# TestBoard.net
KiCad netlist of a schematic drawn in Altium Designer
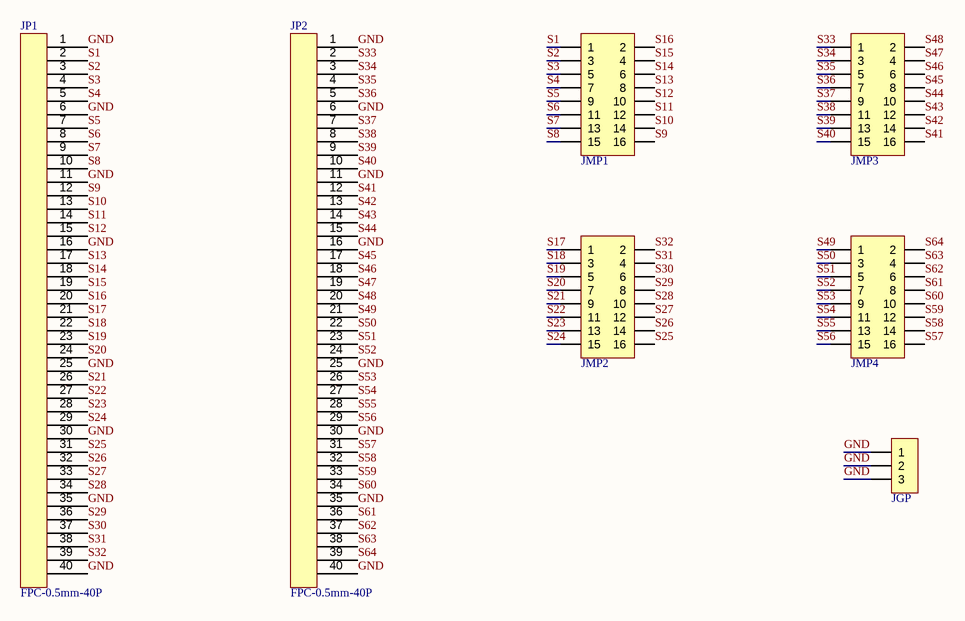
[diagram p0: TestBoard.SchDoc]

(export (version "E")
  (design (tool "Eeschema 10.0.6"))
  (components
    (comp (ref "JGP")
      (value "HDR-1X3")
      (footprint "XH2.54-LI-3P")
      (description "3P接插件")
      (fields (field (name "版权归属") "封装库来自淘宝 ID：黄晶宝石"))
      (libsource (lib "5.4 - 接插件-脚距2.54 (100mil) ") (part "Header 3"))
    )
    (comp (ref "JMP1")
      (value "Header 8X2")
      (footprint "IDC2.54-LI-2x8P")
      (description "8*2P接插件")
      (fields (field (name "版权归属") "封装库来自淘宝 ID：黄晶宝石"))
      (libsource (lib "5.4 - 接插件-脚距2.54 (100mil) ") (part "Header 8X2"))
    )
    (comp (ref "JMP2")
      (value "Header 8X2")
      (footprint "IDC2.54-LI-2x8P")
      (description "8*2P接插件")
      (fields (field (name "版权归属") "封装库来自淘宝 ID：黄晶宝石"))
      (libsource (lib "5.4 - 接插件-脚距2.54 (100mil) ") (part "Header 8X2"))
    )
    (comp (ref "JMP3")
      (value "Header 8X2")
      (footprint "IDC2.54-LI-2x8P")
      (description "8*2P接插件")
      (fields (field (name "版权归属") "封装库来自淘宝 ID：黄晶宝石"))
      (libsource (lib "5.4 - 接插件-脚距2.54 (100mil) ") (part "Header 8X2"))
    )
    (comp (ref "JMP4")
      (value "Header 8X2")
      (footprint "IDC2.54-LI-2x8P")
      (description "8*2P接插件")
      (fields (field (name "版权归属") "封装库来自淘宝 ID：黄晶宝石"))
      (libsource (lib "5.4 - 接插件-脚距2.54 (100mil) ") (part "Header 8X2"))
    )
    (comp (ref "JP1")
      (value "FPC-0.5mm-40P")
      (footprint "FPC0.5 2H-WS-40P")
      (description "FPC Connector 0.5mm 40PIN")
      (libsource (lib "CustomizedComponents") (part "FPC-0.5mm-40P"))
    )
    (comp (ref "JP2")
      (value "FPC-0.5mm-40P")
      (footprint "FPC0.5 2H-WS-40P")
      (description "FPC Connector 0.5mm 40PIN")
      (libsource (lib "CustomizedComponents") (part "FPC-0.5mm-40P"))
    )
  )
  (nets
    (net (code "1") (name "/GND") (class "Default")
      (node (ref "JGP") (pin "1") (pinfunction "1_1") (pintype "passive"))
      (node (ref "JGP") (pin "2") (pinfunction "2_2") (pintype "passive"))
      (node (ref "JGP") (pin "3") (pinfunction "3_3") (pintype "passive"))
      (node (ref "JP1") (pin "1") (pintype "passive"))
      (node (ref "JP1") (pin "11") (pintype "passive"))
      (node (ref "JP1") (pin "16") (pintype "passive"))
      (node (ref "JP1") (pin "25") (pintype "passive"))
      (node (ref "JP1") (pin "30") (pintype "passive"))
      (node (ref "JP1") (pin "35") (pintype "passive"))
      (node (ref "JP1") (pin "40") (pintype "passive"))
      (node (ref "JP1") (pin "6") (pintype "passive"))
      (node (ref "JP2") (pin "1") (pintype "passive"))
      (node (ref "JP2") (pin "11") (pintype "passive"))
      (node (ref "JP2") (pin "16") (pintype "passive"))
      (node (ref "JP2") (pin "25") (pintype "passive"))
      (node (ref "JP2") (pin "30") (pintype "passive"))
      (node (ref "JP2") (pin "35") (pintype "passive"))
      (node (ref "JP2") (pin "40") (pintype "passive"))
      (node (ref "JP2") (pin "6") (pintype "passive"))
    )
    (net (code "2") (name "/S1") (class "Default")
      (node (ref "JMP1") (pin "1") (pinfunction "1_1") (pintype "passive"))
      (node (ref "JP1") (pin "2") (pintype "passive"))
    )
    (net (code "3") (name "/S2") (class "Default")
      (node (ref "JMP1") (pin "3") (pinfunction "3_3") (pintype "passive"))
      (node (ref "JP1") (pin "3") (pintype "passive"))
    )
    (net (code "4") (name "/S3") (class "Default")
      (node (ref "JMP1") (pin "5") (pinfunction "5_5") (pintype "passive"))
      (node (ref "JP1") (pin "4") (pintype "passive"))
    )
    (net (code "5") (name "/S4") (class "Default")
      (node (ref "JMP1") (pin "7") (pinfunction "7_7") (pintype "passive"))
      (node (ref "JP1") (pin "5") (pintype "passive"))
    )
    (net (code "6") (name "/S5") (class "Default")
      (node (ref "JMP1") (pin "9") (pinfunction "9_9") (pintype "passive"))
      (node (ref "JP1") (pin "7") (pintype "passive"))
    )
    (net (code "7") (name "/S6") (class "Default")
      (node (ref "JMP1") (pin "11") (pinfunction "11_11") (pintype "passive"))
      (node (ref "JP1") (pin "8") (pintype "passive"))
    )
    (net (code "8") (name "/S7") (class "Default")
      (node (ref "JMP1") (pin "13") (pinfunction "13_13") (pintype "passive"))
      (node (ref "JP1") (pin "9") (pintype "passive"))
    )
    (net (code "9") (name "/S8") (class "Default")
      (node (ref "JMP1") (pin "15") (pinfunction "15_15") (pintype "passive"))
      (node (ref "JP1") (pin "10") (pintype "passive"))
    )
    (net (code "10") (name "/S9") (class "Default")
      (node (ref "JMP1") (pin "16") (pinfunction "16_16") (pintype "passive"))
      (node (ref "JP1") (pin "12") (pintype "passive"))
    )
    (net (code "11") (name "/S10") (class "Default")
      (node (ref "JMP1") (pin "14") (pinfunction "14_14") (pintype "passive"))
      (node (ref "JP1") (pin "13") (pintype "passive"))
    )
    (net (code "12") (name "/S11") (class "Default")
      (node (ref "JMP1") (pin "12") (pinfunction "12_12") (pintype "passive"))
      (node (ref "JP1") (pin "14") (pintype "passive"))
    )
    (net (code "13") (name "/S12") (class "Default")
      (node (ref "JMP1") (pin "10") (pinfunction "10_10") (pintype "passive"))
      (node (ref "JP1") (pin "15") (pintype "passive"))
    )
    (net (code "14") (name "/S13") (class "Default")
      (node (ref "JMP1") (pin "8") (pinfunction "8_8") (pintype "passive"))
      (node (ref "JP1") (pin "17") (pintype "passive"))
    )
    (net (code "15") (name "/S14") (class "Default")
      (node (ref "JMP1") (pin "6") (pinfunction "6_6") (pintype "passive"))
      (node (ref "JP1") (pin "18") (pintype "passive"))
    )
    (net (code "16") (name "/S15") (class "Default")
      (node (ref "JMP1") (pin "4") (pinfunction "4_4") (pintype "passive"))
      (node (ref "JP1") (pin "19") (pintype "passive"))
    )
    (net (code "17") (name "/S16") (class "Default")
      (node (ref "JMP1") (pin "2") (pinfunction "2_2") (pintype "passive"))
      (node (ref "JP1") (pin "20") (pintype "passive"))
    )
    (net (code "18") (name "/S17") (class "Default")
      (node (ref "JMP2") (pin "1") (pinfunction "1_1") (pintype "passive"))
      (node (ref "JP1") (pin "21") (pintype "passive"))
    )
    (net (code "19") (name "/S18") (class "Default")
      (node (ref "JMP2") (pin "3") (pinfunction "3_3") (pintype "passive"))
      (node (ref "JP1") (pin "22") (pintype "passive"))
    )
    (net (code "20") (name "/S19") (class "Default")
      (node (ref "JMP2") (pin "5") (pinfunction "5_5") (pintype "passive"))
      (node (ref "JP1") (pin "23") (pintype "passive"))
    )
    (net (code "21") (name "/S20") (class "Default")
      (node (ref "JMP2") (pin "7") (pinfunction "7_7") (pintype "passive"))
      (node (ref "JP1") (pin "24") (pintype "passive"))
    )
    (net (code "22") (name "/S21") (class "Default")
      (node (ref "JMP2") (pin "9") (pinfunction "9_9") (pintype "passive"))
      (node (ref "JP1") (pin "26") (pintype "passive"))
    )
    (net (code "23") (name "/S22") (class "Default")
      (node (ref "JMP2") (pin "11") (pinfunction "11_11") (pintype "passive"))
      (node (ref "JP1") (pin "27") (pintype "passive"))
    )
    (net (code "24") (name "/S23") (class "Default")
      (node (ref "JMP2") (pin "13") (pinfunction "13_13") (pintype "passive"))
      (node (ref "JP1") (pin "28") (pintype "passive"))
    )
    (net (code "25") (name "/S24") (class "Default")
      (node (ref "JMP2") (pin "15") (pinfunction "15_15") (pintype "passive"))
      (node (ref "JP1") (pin "29") (pintype "passive"))
    )
    (net (code "26") (name "/S25") (class "Default")
      (node (ref "JMP2") (pin "16") (pinfunction "16_16") (pintype "passive"))
      (node (ref "JP1") (pin "31") (pintype "passive"))
    )
    (net (code "27") (name "/S26") (class "Default")
      (node (ref "JMP2") (pin "14") (pinfunction "14_14") (pintype "passive"))
      (node (ref "JP1") (pin "32") (pintype "passive"))
    )
    (net (code "28") (name "/S27") (class "Default")
      (node (ref "JMP2") (pin "12") (pinfunction "12_12") (pintype "passive"))
      (node (ref "JP1") (pin "33") (pintype "passive"))
    )
    (net (code "29") (name "/S28") (class "Default")
      (node (ref "JMP2") (pin "10") (pinfunction "10_10") (pintype "passive"))
      (node (ref "JP1") (pin "34") (pintype "passive"))
    )
    (net (code "30") (name "/S29") (class "Default")
      (node (ref "JMP2") (pin "8") (pinfunction "8_8") (pintype "passive"))
      (node (ref "JP1") (pin "36") (pintype "passive"))
    )
    (net (code "31") (name "/S30") (class "Default")
      (node (ref "JMP2") (pin "6") (pinfunction "6_6") (pintype "passive"))
      (node (ref "JP1") (pin "37") (pintype "passive"))
    )
    (net (code "32") (name "/S31") (class "Default")
      (node (ref "JMP2") (pin "4") (pinfunction "4_4") (pintype "passive"))
      (node (ref "JP1") (pin "38") (pintype "passive"))
    )
    (net (code "33") (name "/S32") (class "Default")
      (node (ref "JMP2") (pin "2") (pinfunction "2_2") (pintype "passive"))
      (node (ref "JP1") (pin "39") (pintype "passive"))
    )
    (net (code "34") (name "/S33") (class "Default")
      (node (ref "JMP3") (pin "1") (pinfunction "1_1") (pintype "passive"))
      (node (ref "JP2") (pin "2") (pintype "passive"))
    )
    (net (code "35") (name "/S34") (class "Default")
      (node (ref "JMP3") (pin "3") (pinfunction "3_3") (pintype "passive"))
      (node (ref "JP2") (pin "3") (pintype "passive"))
    )
    (net (code "36") (name "/S35") (class "Default")
      (node (ref "JMP3") (pin "5") (pinfunction "5_5") (pintype "passive"))
      (node (ref "JP2") (pin "4") (pintype "passive"))
    )
    (net (code "37") (name "/S36") (class "Default")
      (node (ref "JMP3") (pin "7") (pinfunction "7_7") (pintype "passive"))
      (node (ref "JP2") (pin "5") (pintype "passive"))
    )
    (net (code "38") (name "/S37") (class "Default")
      (node (ref "JMP3") (pin "9") (pinfunction "9_9") (pintype "passive"))
      (node (ref "JP2") (pin "7") (pintype "passive"))
    )
    (net (code "39") (name "/S38") (class "Default")
      (node (ref "JMP3") (pin "11") (pinfunction "11_11") (pintype "passive"))
      (node (ref "JP2") (pin "8") (pintype "passive"))
    )
    (net (code "40") (name "/S39") (class "Default")
      (node (ref "JMP3") (pin "13") (pinfunction "13_13") (pintype "passive"))
      (node (ref "JP2") (pin "9") (pintype "passive"))
    )
    (net (code "41") (name "/S40") (class "Default")
      (node (ref "JMP3") (pin "15") (pinfunction "15_15") (pintype "passive"))
      (node (ref "JP2") (pin "10") (pintype "passive"))
    )
    (net (code "42") (name "/S41") (class "Default")
      (node (ref "JMP3") (pin "16") (pinfunction "16_16") (pintype "passive"))
      (node (ref "JP2") (pin "12") (pintype "passive"))
    )
    (net (code "43") (name "/S42") (class "Default")
      (node (ref "JMP3") (pin "14") (pinfunction "14_14") (pintype "passive"))
      (node (ref "JP2") (pin "13") (pintype "passive"))
    )
    (net (code "44") (name "/S43") (class "Default")
      (node (ref "JMP3") (pin "12") (pinfunction "12_12") (pintype "passive"))
      (node (ref "JP2") (pin "14") (pintype "passive"))
    )
    (net (code "45") (name "/S44") (class "Default")
      (node (ref "JMP3") (pin "10") (pinfunction "10_10") (pintype "passive"))
      (node (ref "JP2") (pin "15") (pintype "passive"))
    )
    (net (code "46") (name "/S45") (class "Default")
      (node (ref "JMP3") (pin "8") (pinfunction "8_8") (pintype "passive"))
      (node (ref "JP2") (pin "17") (pintype "passive"))
    )
    (net (code "47") (name "/S46") (class "Default")
      (node (ref "JMP3") (pin "6") (pinfunction "6_6") (pintype "passive"))
      (node (ref "JP2") (pin "18") (pintype "passive"))
    )
    (net (code "48") (name "/S47") (class "Default")
      (node (ref "JMP3") (pin "4") (pinfunction "4_4") (pintype "passive"))
      (node (ref "JP2") (pin "19") (pintype "passive"))
    )
    (net (code "49") (name "/S48") (class "Default")
      (node (ref "JMP3") (pin "2") (pinfunction "2_2") (pintype "passive"))
      (node (ref "JP2") (pin "20") (pintype "passive"))
    )
    (net (code "50") (name "/S49") (class "Default")
      (node (ref "JMP4") (pin "1") (pinfunction "1_1") (pintype "passive"))
      (node (ref "JP2") (pin "21") (pintype "passive"))
    )
    (net (code "51") (name "/S50") (class "Default")
      (node (ref "JMP4") (pin "3") (pinfunction "3_3") (pintype "passive"))
      (node (ref "JP2") (pin "22") (pintype "passive"))
    )
    (net (code "52") (name "/S51") (class "Default")
      (node (ref "JMP4") (pin "5") (pinfunction "5_5") (pintype "passive"))
      (node (ref "JP2") (pin "23") (pintype "passive"))
    )
    (net (code "53") (name "/S52") (class "Default")
      (node (ref "JMP4") (pin "7") (pinfunction "7_7") (pintype "passive"))
      (node (ref "JP2") (pin "24") (pintype "passive"))
    )
    (net (code "54") (name "/S53") (class "Default")
      (node (ref "JMP4") (pin "9") (pinfunction "9_9") (pintype "passive"))
      (node (ref "JP2") (pin "26") (pintype "passive"))
    )
    (net (code "55") (name "/S54") (class "Default")
      (node (ref "JMP4") (pin "11") (pinfunction "11_11") (pintype "passive"))
      (node (ref "JP2") (pin "27") (pintype "passive"))
    )
    (net (code "56") (name "/S55") (class "Default")
      (node (ref "JMP4") (pin "13") (pinfunction "13_13") (pintype "passive"))
      (node (ref "JP2") (pin "28") (pintype "passive"))
    )
    (net (code "57") (name "/S56") (class "Default")
      (node (ref "JMP4") (pin "15") (pinfunction "15_15") (pintype "passive"))
      (node (ref "JP2") (pin "29") (pintype "passive"))
    )
    (net (code "58") (name "/S57") (class "Default")
      (node (ref "JMP4") (pin "16") (pinfunction "16_16") (pintype "passive"))
      (node (ref "JP2") (pin "31") (pintype "passive"))
    )
    (net (code "59") (name "/S58") (class "Default")
      (node (ref "JMP4") (pin "14") (pinfunction "14_14") (pintype "passive"))
      (node (ref "JP2") (pin "32") (pintype "passive"))
    )
    (net (code "60") (name "/S59") (class "Default")
      (node (ref "JMP4") (pin "12") (pinfunction "12_12") (pintype "passive"))
      (node (ref "JP2") (pin "33") (pintype "passive"))
    )
    (net (code "61") (name "/S60") (class "Default")
      (node (ref "JMP4") (pin "10") (pinfunction "10_10") (pintype "passive"))
      (node (ref "JP2") (pin "34") (pintype "passive"))
    )
    (net (code "62") (name "/S61") (class "Default")
      (node (ref "JMP4") (pin "8") (pinfunction "8_8") (pintype "passive"))
      (node (ref "JP2") (pin "36") (pintype "passive"))
    )
    (net (code "63") (name "/S62") (class "Default")
      (node (ref "JMP4") (pin "6") (pinfunction "6_6") (pintype "passive"))
      (node (ref "JP2") (pin "37") (pintype "passive"))
    )
    (net (code "64") (name "/S63") (class "Default")
      (node (ref "JMP4") (pin "4") (pinfunction "4_4") (pintype "passive"))
      (node (ref "JP2") (pin "38") (pintype "passive"))
    )
    (net (code "65") (name "/S64") (class "Default")
      (node (ref "JMP4") (pin "2") (pinfunction "2_2") (pintype "passive"))
      (node (ref "JP2") (pin "39") (pintype "passive"))
    )
  )
)
